# CYUSB.net
KiCad netlist of a schematic drawn in Altium Designer
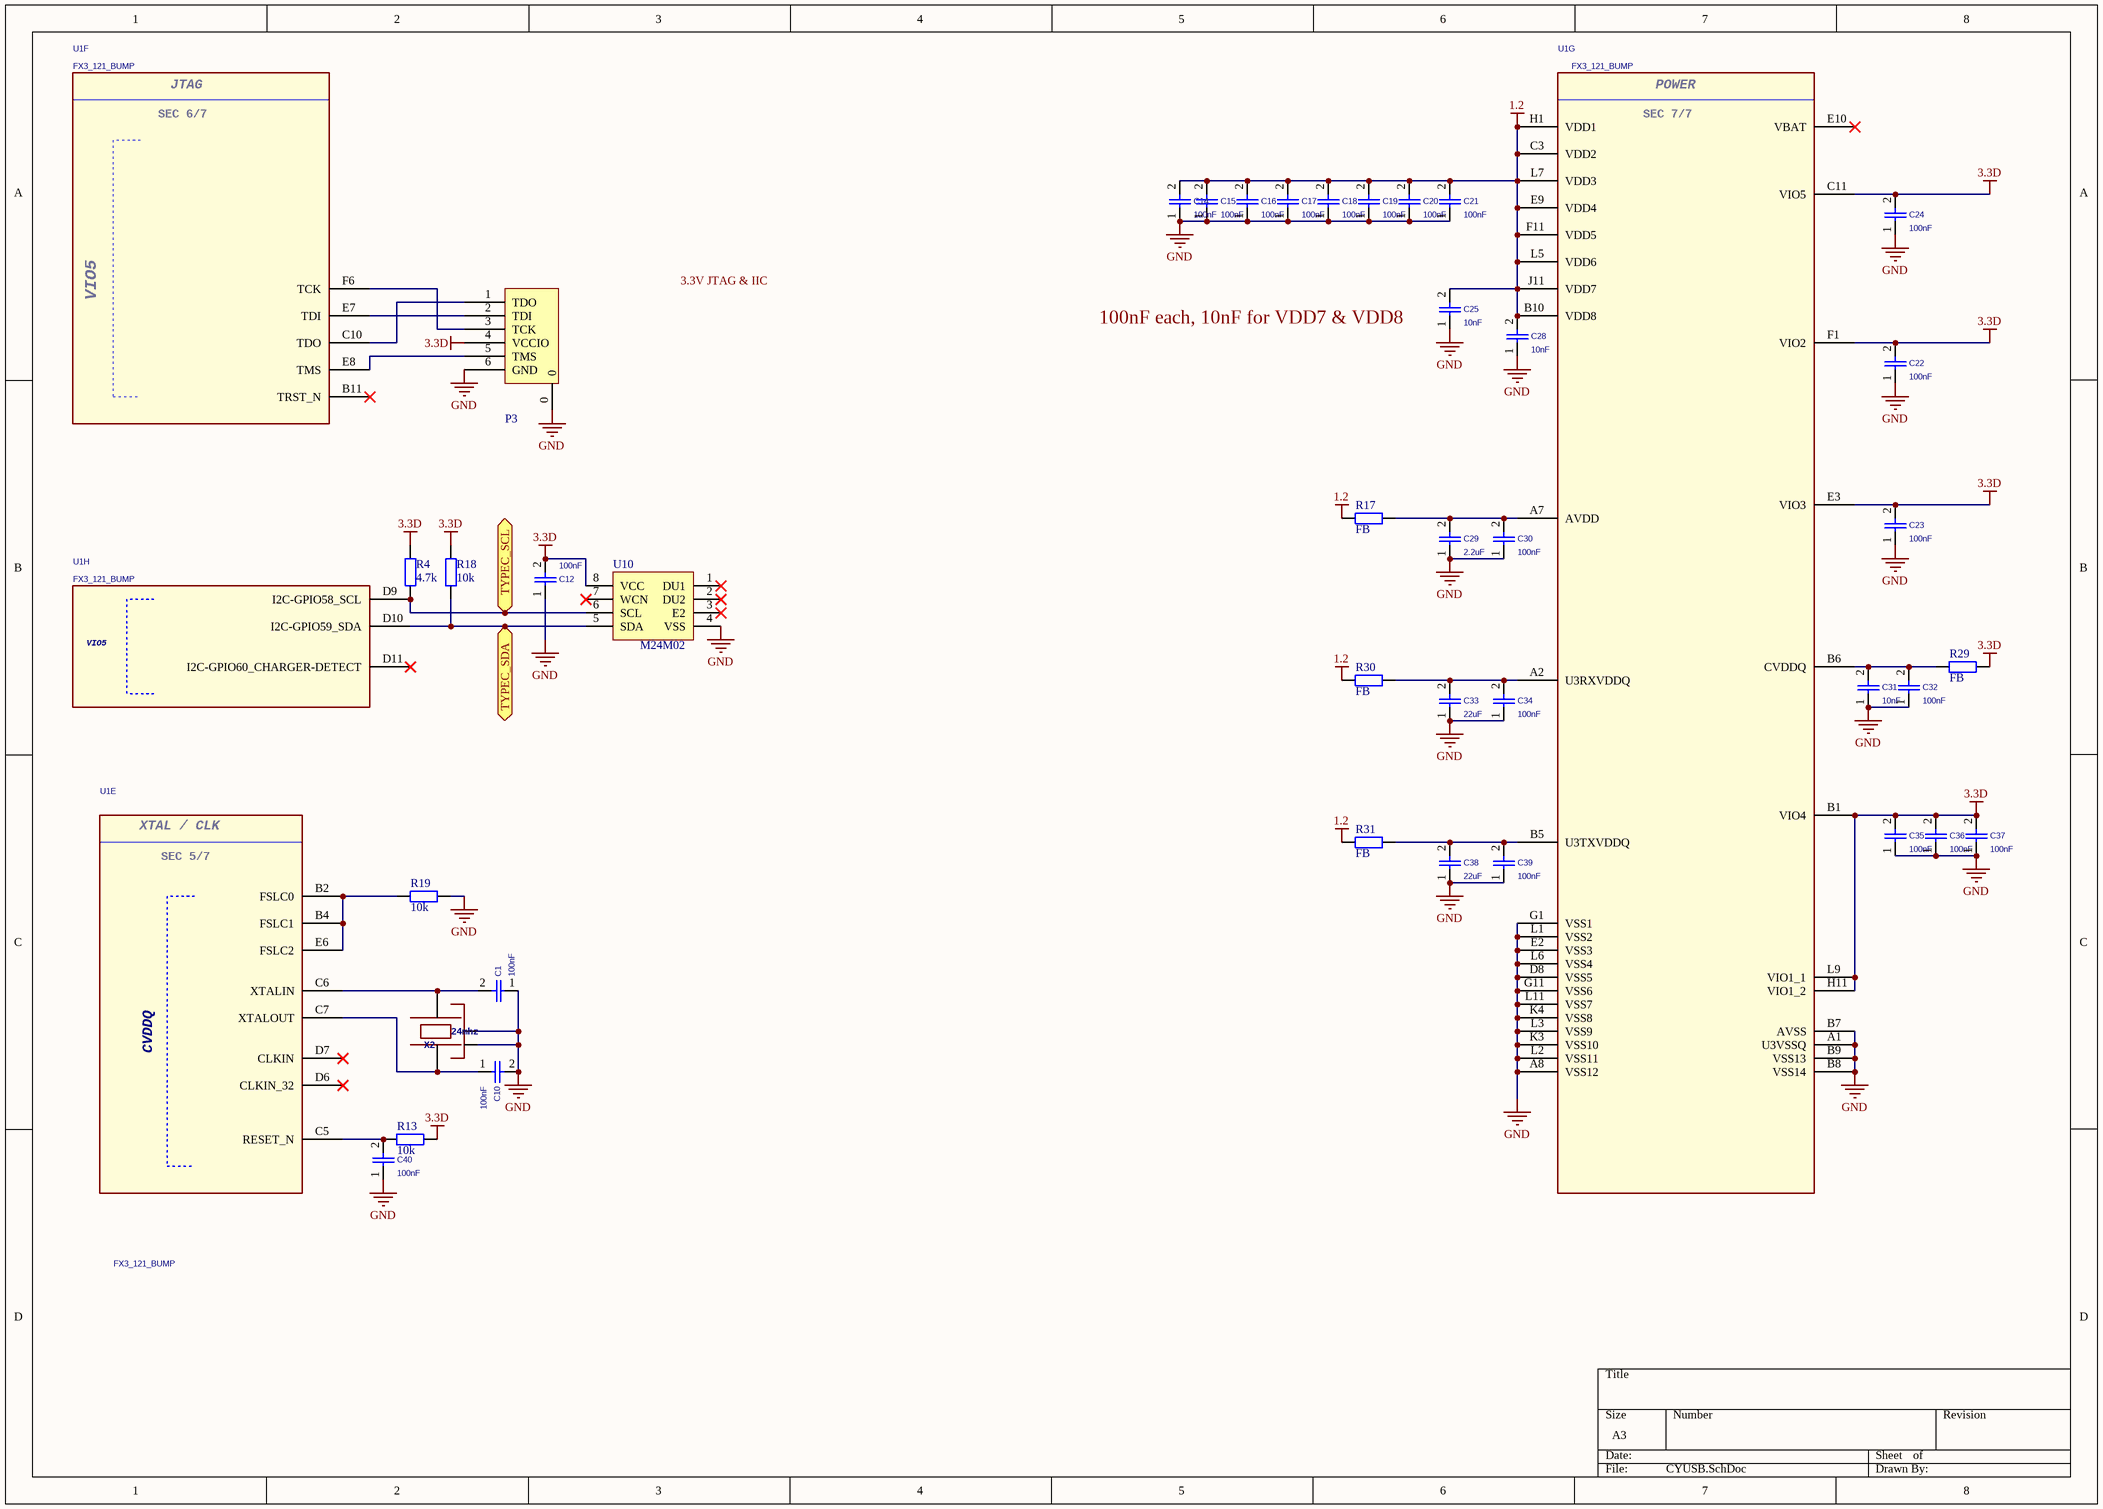
[diagram p0: CYUSB.SchDoc]

(export (version "E")
  (design (tool "Eeschema 10.0.6"))
  (components
    (comp (ref "C1") (value "100nF") (footprint "0201") (libsource (lib "*") (part "CAP/0402")))
    (comp (ref "C10") (value "100nF") (footprint "0201") (libsource (lib "*") (part "CAP/0402")))
    (comp (ref "C12") (value "100nF") (footprint "0201") (libsource (lib "*") (part "CAP/0402")))
    (comp (ref "C14") (value "100nF") (footprint "0201") (libsource (lib "*") (part "CAP/0402")))
    (comp (ref "C15") (value "100nF") (footprint "0201") (libsource (lib "*") (part "CAP/0402")))
    (comp (ref "C16") (value "100nF") (footprint "0201") (libsource (lib "*") (part "CAP/0402")))
    (comp (ref "C17") (value "100nF") (footprint "0201") (libsource (lib "*") (part "CAP/0402")))
    (comp (ref "C18") (value "100nF") (footprint "0201") (libsource (lib "*") (part "CAP/0402")))
    (comp (ref "C19") (value "100nF") (footprint "0201") (libsource (lib "*") (part "CAP/0402")))
    (comp (ref "C20") (value "100nF") (footprint "0201") (libsource (lib "*") (part "CAP/0402")))
    (comp (ref "C21") (value "100nF") (footprint "0201") (libsource (lib "*") (part "CAP/0402")))
    (comp (ref "C22") (value "100nF") (footprint "0201") (libsource (lib "*") (part "CAP/0402")))
    (comp (ref "C23") (value "100nF") (footprint "0201") (libsource (lib "*") (part "CAP/0402")))
    (comp (ref "C24") (value "100nF") (footprint "0201") (libsource (lib "*") (part "CAP/0402")))
    (comp (ref "C25") (value "10nF") (footprint "0201") (libsource (lib "*") (part "CAP/0402")))
    (comp (ref "C28") (value "10nF") (footprint "0201") (libsource (lib "*") (part "CAP/0402")))
    (comp (ref "C29") (value "2.2uF") (footprint "0201") (libsource (lib "*") (part "CAP/0402")))
    (comp (ref "C30") (value "100nF") (footprint "0201") (libsource (lib "*") (part "CAP/0402")))
    (comp (ref "C31") (value "10nF") (footprint "0201") (libsource (lib "*") (part "CAP/0402")))
    (comp (ref "C32") (value "100nF") (footprint "0201") (libsource (lib "*") (part "CAP/0402")))
    (comp (ref "C33") (value "22uF") (footprint "0603L") (libsource (lib "*") (part "CAP/0402")))
    (comp (ref "C34") (value "100nF") (footprint "0201") (libsource (lib "*") (part "CAP/0402")))
    (comp (ref "C35") (value "100nF") (footprint "0201") (libsource (lib "*") (part "CAP/0402")))
    (comp (ref "C36") (value "100nF") (footprint "0201") (libsource (lib "*") (part "CAP/0402")))
    (comp (ref "C37") (value "100nF") (footprint "0201") (libsource (lib "*") (part "CAP/0402")))
    (comp (ref "C38") (value "22uF") (footprint "0603L") (libsource (lib "*") (part "CAP/0402")))
    (comp (ref "C39") (value "100nF") (footprint "0201") (libsource (lib "*") (part "CAP/0402")))
    (comp (ref "C40") (value "100nF") (footprint "0201") (libsource (lib "*") (part "CAP/0402")))
    (comp (ref "P3") (value "JTAG-6P") (footprint "GH1.25-6") (libsource (lib "sch") (part "JTAG-6P")))
    (comp (ref "R4")
      (value "4.7k")
      (footprint "0201")
      (description "Resistor")
      (fields (field (name "PUBLISHER") "Altium Limited"))
      (libsource (lib "RTC6705") (part "Res2"))
    )
    (comp (ref "R13")
      (value "10k")
      (footprint "0201")
      (description "Resistor")
      (fields (field (name "PUBLISHER") "Altium Limited"))
      (libsource (lib "") (part "Res2_1"))
    )
    (comp (ref "R17")
      (value "FB")
      (footprint "0402")
      (description "Resistor")
      (fields (field (name "PUBLISHER") "Altium Limited"))
      (libsource (lib "") (part "Res2_2"))
    )
    (comp (ref "R18")
      (value "10k")
      (footprint "0201")
      (description "Resistor")
      (fields (field (name "PUBLISHER") "Altium Limited"))
      (libsource (lib "RTC6705") (part "Res2"))
    )
    (comp (ref "R19")
      (value "10k")
      (footprint "0201")
      (description "Resistor")
      (fields (field (name "PUBLISHER") "Altium Limited"))
      (libsource (lib "") (part "Res2_1"))
    )
    (comp (ref "R29")
      (value "FB")
      (footprint "0402")
      (description "Resistor")
      (fields (field (name "PUBLISHER") "Altium Limited"))
      (libsource (lib "") (part "Res2_2"))
    )
    (comp (ref "R30")
      (value "FB")
      (footprint "0402")
      (description "Resistor")
      (fields (field (name "PUBLISHER") "Altium Limited"))
      (libsource (lib "") (part "Res2_2"))
    )
    (comp (ref "R31")
      (value "FB")
      (footprint "0402")
      (description "Resistor")
      (fields (field (name "PUBLISHER") "Altium Limited"))
      (libsource (lib "") (part "Res2_2"))
    )
    (comp (ref "U1")
      (value "FX3_121_BUMP")
      (footprint "FX3_121_BUMP")
      (description "FX3")
      (fields (field (name "MANUFACTURER") "Cypress"))
      (libsource (lib "cyusb3014") (part "FX3_121_BUMP_10"))
    )
    (comp (ref "U10") (value "M24M02") (footprint "SO8") (libsource (lib "cyusb3014") (part "M24M02")))
    (comp (ref "X2")
      (value "24mhz")
      (footprint "OSCILLATOR-2.5x2.0")
      (description "Crystal Oscillator in 3.2x2.5 SMD")
      (libsource (lib "sch") (part "OSCILLATOR-3.2X2.5"))
    )
  )
  (nets
    (net (code "2") (name "/TYPEC_SCL") (class "Default")
      (node (ref "R4") (pin "1") (pinfunction "1_1") (pintype "passive"))
      (node (ref "U1") (pin "D9") (pinfunction "I2C-GPIO58_SCL_D9") (pintype "passive"))
      (node (ref "U10") (pin "6") (pinfunction "SCL_6") (pintype "passive"))
    )
    (net (code "3") (name "/TYPEC_SDA") (class "Default")
      (node (ref "R18") (pin "1") (pinfunction "1_1") (pintype "passive"))
      (node (ref "U1") (pin "D10") (pinfunction "I2C-GPIO59_SDA_D10") (pintype "passive"))
      (node (ref "U10") (pin "5") (pinfunction "SDA_5") (pintype "passive"))
    )
    (net (code "4") (name "1.2") (class "Default")
      (node (ref "C14") (pin "2") (pinfunction "2_2") (pintype "passive"))
      (node (ref "C15") (pin "2") (pinfunction "2_2") (pintype "passive"))
      (node (ref "C16") (pin "2") (pinfunction "2_2") (pintype "passive"))
      (node (ref "C17") (pin "2") (pinfunction "2_2") (pintype "passive"))
      (node (ref "C18") (pin "2") (pinfunction "2_2") (pintype "passive"))
      (node (ref "C19") (pin "2") (pinfunction "2_2") (pintype "passive"))
      (node (ref "C20") (pin "2") (pinfunction "2_2") (pintype "passive"))
      (node (ref "C21") (pin "2") (pinfunction "2_2") (pintype "passive"))
      (node (ref "C25") (pin "2") (pinfunction "2_2") (pintype "passive"))
      (node (ref "C28") (pin "2") (pinfunction "2_2") (pintype "passive"))
      (node (ref "R17") (pin "2") (pinfunction "2_2") (pintype "passive"))
      (node (ref "R30") (pin "2") (pinfunction "2_2") (pintype "passive"))
      (node (ref "R31") (pin "2") (pinfunction "2_2") (pintype "passive"))
      (node (ref "U1") (pin "B10") (pinfunction "VDD8_B10") (pintype "passive"))
      (node (ref "U1") (pin "C3") (pinfunction "VDD2_C3") (pintype "passive"))
      (node (ref "U1") (pin "E9") (pinfunction "VDD4_E9") (pintype "passive"))
      (node (ref "U1") (pin "F11") (pinfunction "VDD5_F11") (pintype "passive"))
      (node (ref "U1") (pin "H1") (pinfunction "VDD1_H1") (pintype "passive"))
      (node (ref "U1") (pin "J11") (pinfunction "VDD7_J11") (pintype "passive"))
      (node (ref "U1") (pin "L5") (pinfunction "VDD6_L5") (pintype "passive"))
      (node (ref "U1") (pin "L7") (pinfunction "VDD3_L7") (pintype "passive"))
    )
    (net (code "5") (name "3.3D") (class "Default")
      (node (ref "C12") (pin "2") (pinfunction "2_2") (pintype "passive"))
      (node (ref "C22") (pin "2") (pinfunction "2_2") (pintype "passive"))
      (node (ref "C23") (pin "2") (pinfunction "2_2") (pintype "passive"))
      (node (ref "C24") (pin "2") (pinfunction "2_2") (pintype "passive"))
      (node (ref "C35") (pin "2") (pinfunction "2_2") (pintype "passive"))
      (node (ref "C36") (pin "2") (pinfunction "2_2") (pintype "passive"))
      (node (ref "C37") (pin "2") (pinfunction "2_2") (pintype "passive"))
      (node (ref "P3") (pin "4") (pinfunction "VCCIO_4") (pintype "passive"))
      (node (ref "R13") (pin "2") (pinfunction "2_2") (pintype "passive"))
      (node (ref "R18") (pin "2") (pinfunction "2_2") (pintype "passive"))
      (node (ref "R29") (pin "1") (pinfunction "1_1") (pintype "passive"))
      (node (ref "R4") (pin "2") (pinfunction "2_2") (pintype "passive"))
      (node (ref "U1") (pin "B1") (pinfunction "VIO4_B1") (pintype "passive"))
      (node (ref "U1") (pin "C11") (pinfunction "VIO5_C11") (pintype "passive"))
      (node (ref "U1") (pin "E3") (pinfunction "VIO3_E3") (pintype "passive"))
      (node (ref "U1") (pin "F1") (pinfunction "VIO2_F1") (pintype "passive"))
      (node (ref "U1") (pin "H11") (pinfunction "VIO1_2_H11") (pintype "passive"))
      (node (ref "U1") (pin "L9") (pinfunction "VIO1_1_L9") (pintype "passive"))
      (node (ref "U10") (pin "8") (pinfunction "VCC_8") (pintype "passive"))
    )
    (net (code "6") (name "GND") (class "Default")
      (node (ref "C1") (pin "1") (pinfunction "1_1") (pintype "passive"))
      (node (ref "C10") (pin "2") (pinfunction "2_2") (pintype "passive"))
      (node (ref "C12") (pin "1") (pinfunction "1_1") (pintype "passive"))
      (node (ref "C14") (pin "1") (pinfunction "1_1") (pintype "passive"))
      (node (ref "C15") (pin "1") (pinfunction "1_1") (pintype "passive"))
      (node (ref "C16") (pin "1") (pinfunction "1_1") (pintype "passive"))
      (node (ref "C17") (pin "1") (pinfunction "1_1") (pintype "passive"))
      (node (ref "C18") (pin "1") (pinfunction "1_1") (pintype "passive"))
      (node (ref "C19") (pin "1") (pinfunction "1_1") (pintype "passive"))
      (node (ref "C20") (pin "1") (pinfunction "1_1") (pintype "passive"))
      (node (ref "C21") (pin "1") (pinfunction "1_1") (pintype "passive"))
      (node (ref "C22") (pin "1") (pinfunction "1_1") (pintype "passive"))
      (node (ref "C23") (pin "1") (pinfunction "1_1") (pintype "passive"))
      (node (ref "C24") (pin "1") (pinfunction "1_1") (pintype "passive"))
      (node (ref "C25") (pin "1") (pinfunction "1_1") (pintype "passive"))
      (node (ref "C28") (pin "1") (pinfunction "1_1") (pintype "passive"))
      (node (ref "C29") (pin "1") (pinfunction "1_1") (pintype "passive"))
      (node (ref "C30") (pin "1") (pinfunction "1_1") (pintype "passive"))
      (node (ref "C31") (pin "1") (pinfunction "1_1") (pintype "passive"))
      (node (ref "C32") (pin "1") (pinfunction "1_1") (pintype "passive"))
      (node (ref "C33") (pin "1") (pinfunction "1_1") (pintype "passive"))
      (node (ref "C34") (pin "1") (pinfunction "1_1") (pintype "passive"))
      (node (ref "C35") (pin "1") (pinfunction "1_1") (pintype "passive"))
      (node (ref "C36") (pin "1") (pinfunction "1_1") (pintype "passive"))
      (node (ref "C37") (pin "1") (pinfunction "1_1") (pintype "passive"))
      (node (ref "C38") (pin "1") (pinfunction "1_1") (pintype "passive"))
      (node (ref "C39") (pin "1") (pinfunction "1_1") (pintype "passive"))
      (node (ref "C40") (pin "1") (pinfunction "1_1") (pintype "passive"))
      (node (ref "P3") (pin "0") (pinfunction "0_0") (pintype "passive"))
      (node (ref "P3") (pin "6") (pinfunction "GND_6") (pintype "passive"))
      (node (ref "R19") (pin "2") (pinfunction "2_2") (pintype "passive"))
      (node (ref "U1") (pin "A1") (pinfunction "U3VSSQ_A1") (pintype "passive"))
      (node (ref "U1") (pin "A8") (pinfunction "VSS12_A8") (pintype "passive"))
      (node (ref "U1") (pin "B7") (pinfunction "AVSS_B7") (pintype "passive"))
      (node (ref "U1") (pin "B8") (pinfunction "VSS14_B8") (pintype "passive"))
      (node (ref "U1") (pin "B9") (pinfunction "VSS13_B9") (pintype "passive"))
      (node (ref "U1") (pin "D8") (pinfunction "VSS5_D8") (pintype "passive"))
      (node (ref "U1") (pin "E2") (pinfunction "VSS3_E2") (pintype "passive"))
      (node (ref "U1") (pin "G1") (pinfunction "VSS1_G1") (pintype "passive"))
      (node (ref "U1") (pin "G11") (pinfunction "VSS6_G11") (pintype "passive"))
      (node (ref "U1") (pin "K3") (pinfunction "VSS10_K3") (pintype "passive"))
      (node (ref "U1") (pin "K4") (pinfunction "VSS8_K4") (pintype "passive"))
      (node (ref "U1") (pin "L1") (pinfunction "VSS2_L1") (pintype "passive"))
      (node (ref "U1") (pin "L11") (pinfunction "VSS7_L11") (pintype "passive"))
      (node (ref "U1") (pin "L2") (pinfunction "VSS11_L2") (pintype "passive"))
      (node (ref "U1") (pin "L3") (pinfunction "VSS9_L3") (pintype "passive"))
      (node (ref "U1") (pin "L6") (pinfunction "VSS4_L6") (pintype "passive"))
      (node (ref "U10") (pin "4") (pinfunction "VSS_4") (pintype "passive"))
      (node (ref "X2") (pin "2") (pinfunction "NC_2_2") (pintype "open_emitter"))
      (node (ref "X2") (pin "4") (pinfunction "NC_4_4") (pintype "open_emitter"))
    )
    (net (code "7") (name "Net-(P3-TCK)") (class "Default")
      (node (ref "P3") (pin "3") (pinfunction "TCK_3") (pintype "passive"))
      (node (ref "U1") (pin "F6") (pinfunction "TCK_F6") (pintype "passive"))
    )
    (net (code "8") (name "Net-(P3-TDI)") (class "Default")
      (node (ref "P3") (pin "2") (pinfunction "TDI_2") (pintype "passive"))
      (node (ref "U1") (pin "E7") (pinfunction "TDI_E7") (pintype "passive"))
    )
    (net (code "9") (name "Net-(P3-TDO)") (class "Default")
      (node (ref "P3") (pin "1") (pinfunction "TDO_1") (pintype "passive"))
      (node (ref "U1") (pin "C10") (pinfunction "TDO_C10") (pintype "passive"))
    )
    (net (code "10") (name "Net-(P3-TMS)") (class "Default")
      (node (ref "P3") (pin "5") (pinfunction "TMS_5") (pintype "passive"))
      (node (ref "U1") (pin "E8") (pinfunction "TMS_E8") (pintype "passive"))
    )
    (net (code "11") (name "Net-(U1E-FSLC0)") (class "Default")
      (node (ref "R19") (pin "1") (pinfunction "1_1") (pintype "passive"))
      (node (ref "U1") (pin "B2") (pinfunction "FSLC0_B2") (pintype "passive"))
      (node (ref "U1") (pin "B4") (pinfunction "FSLC1_B4") (pintype "passive"))
      (node (ref "U1") (pin "E6") (pinfunction "FSLC2_E6") (pintype "passive"))
    )
    (net (code "12") (name "Net-(U1E-RESET_N)") (class "Default")
      (node (ref "C40") (pin "2") (pinfunction "2_2") (pintype "passive"))
      (node (ref "R13") (pin "1") (pinfunction "1_1") (pintype "passive"))
      (node (ref "U1") (pin "C5") (pinfunction "RESET_N_C5") (pintype "passive"))
    )
    (net (code "13") (name "Net-(U1E-XTALIN)") (class "Default")
      (node (ref "C1") (pin "2") (pinfunction "2_2") (pintype "passive"))
      (node (ref "U1") (pin "C6") (pinfunction "XTALIN_C6") (pintype "passive"))
      (node (ref "X2") (pin "3") (pinfunction "3_3") (pintype "passive"))
    )
    (net (code "14") (name "Net-(U1E-XTALOUT)") (class "Default")
      (node (ref "C10") (pin "1") (pinfunction "1_1") (pintype "passive"))
      (node (ref "U1") (pin "C7") (pinfunction "XTALOUT_C7") (pintype "passive"))
      (node (ref "X2") (pin "1") (pinfunction "1_1") (pintype "passive"))
    )
    (net (code "15") (name "Net-(U1G-AVDD)") (class "Default")
      (node (ref "C29") (pin "2") (pinfunction "2_2") (pintype "passive"))
      (node (ref "C30") (pin "2") (pinfunction "2_2") (pintype "passive"))
      (node (ref "R17") (pin "1") (pinfunction "1_1") (pintype "passive"))
      (node (ref "U1") (pin "A7") (pinfunction "AVDD_A7") (pintype "passive"))
    )
    (net (code "16") (name "Net-(U1G-CVDDQ)") (class "Default")
      (node (ref "C31") (pin "2") (pinfunction "2_2") (pintype "passive"))
      (node (ref "C32") (pin "2") (pinfunction "2_2") (pintype "passive"))
      (node (ref "R29") (pin "2") (pinfunction "2_2") (pintype "passive"))
      (node (ref "U1") (pin "B6") (pinfunction "CVDDQ_B6") (pintype "passive"))
    )
    (net (code "17") (name "Net-(U1G-U3RXVDDQ)") (class "Default")
      (node (ref "C33") (pin "2") (pinfunction "2_2") (pintype "passive"))
      (node (ref "C34") (pin "2") (pinfunction "2_2") (pintype "passive"))
      (node (ref "R30") (pin "1") (pinfunction "1_1") (pintype "passive"))
      (node (ref "U1") (pin "A2") (pinfunction "U3RXVDDQ_A2") (pintype "passive"))
    )
    (net (code "18") (name "Net-(U1G-U3TXVDDQ)") (class "Default")
      (node (ref "C38") (pin "2") (pinfunction "2_2") (pintype "passive"))
      (node (ref "C39") (pin "2") (pinfunction "2_2") (pintype "passive"))
      (node (ref "R31") (pin "1") (pinfunction "1_1") (pintype "passive"))
      (node (ref "U1") (pin "B5") (pinfunction "U3TXVDDQ_B5") (pintype "passive"))
    )
    (net (code "19") (name "unconnected-(U1E-CLKIN-PadD7)") (class "Default")
      (node (ref "U1") (pin "D7") (pinfunction "CLKIN_D7") (pintype "passive+no_connect"))
    )
    (net (code "20") (name "unconnected-(U1E-CLKIN_32-PadD6)") (class "Default")
      (node (ref "U1") (pin "D6") (pinfunction "CLKIN_32_D6") (pintype "passive+no_connect"))
    )
    (net (code "21") (name "unconnected-(U1F-TRST_N-PadB11)") (class "Default")
      (node (ref "U1") (pin "B11") (pinfunction "TRST_N_B11") (pintype "passive+no_connect"))
    )
    (net (code "22") (name "unconnected-(U1G-VBAT-PadE10)") (class "Default")
      (node (ref "U1") (pin "E10") (pinfunction "VBAT_E10") (pintype "passive+no_connect"))
    )
    (net (code "23") (name "unconnected-(U1H-I2C-GPIO60_CHARGER-DETECT-PadD11)") (class "Default")
      (node (ref "U1") (pin "D11") (pinfunction "I2C-GPIO60_CHARGER-DETECT_D11") (pintype "passive+no_connect"))
    )
    (net (code "24") (name "unconnected-(U10-DU1-Pad1)") (class "Default")
      (node (ref "U10") (pin "1") (pinfunction "DU1_1") (pintype "passive+no_connect"))
    )
    (net (code "25") (name "unconnected-(U10-DU2-Pad2)") (class "Default")
      (node (ref "U10") (pin "2") (pinfunction "DU2_2") (pintype "passive+no_connect"))
    )
    (net (code "26") (name "unconnected-(U10-E2-Pad3)") (class "Default")
      (node (ref "U10") (pin "3") (pinfunction "E2_3") (pintype "passive+no_connect"))
    )
    (net (code "27") (name "unconnected-(U10-WCN-Pad7)") (class "Default")
      (node (ref "U10") (pin "7") (pinfunction "WCN_7") (pintype "passive+no_connect"))
    )
  )
)
